# coils.net
KiCad netlist of a schematic drawn in Altium Designer
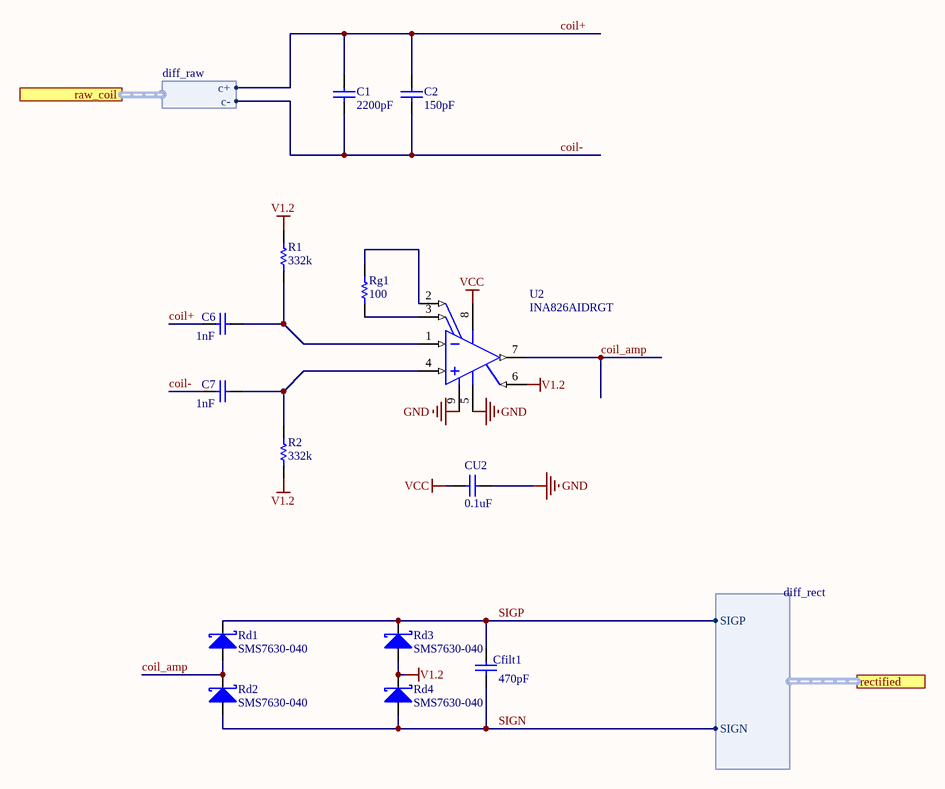
[diagram p0: coils.SchDoc]

(export (version "E")
  (design (tool "Eeschema 10.0.6"))
  (components
    (comp (ref "C1")
      (value "2200pF")
      (footprint "0402")
      (description "Ceramic Capacitor (Surface Mount)")
      (fields (field (name "MANUFACTURER") "Generic Ceramic Chip Cap (TBD)") (field (name "Comment") "Cap"))
      (libsource (lib "maglib") (part "Cap"))
    )
    (comp (ref "C2")
      (value "150pF")
      (footprint "0402")
      (description "Ceramic Capacitor (Surface Mount)")
      (fields (field (name "MANUFACTURER") "Generic Ceramic Chip Cap (TBD)") (field (name "Comment") "Cap"))
      (libsource (lib "maglib") (part "Cap"))
    )
    (comp (ref "C6")
      (value "1nF")
      (footprint "0402")
      (description "Ceramic Capacitor (Surface Mount)")
      (fields (field (name "MANUFACTURER") "Generic Ceramic Chip Cap (TBD)") (field (name "Comment") "Cap"))
      (libsource (lib "maglib") (part "Cap"))
    )
    (comp (ref "C7")
      (value "1nF")
      (footprint "0402")
      (description "Ceramic Capacitor (Surface Mount)")
      (fields (field (name "MANUFACTURER") "Generic Ceramic Chip Cap (TBD)") (field (name "Comment") "Cap"))
      (libsource (lib "maglib") (part "Cap"))
    )
    (comp (ref "Cfilt1")
      (value "470pF")
      (footprint "0402")
      (description "Ceramic Capacitor (Surface Mount)")
      (fields (field (name "MANUFACTURER") "Generic Ceramic Chip Cap (TBD)") (field (name "Comment") "Cap"))
      (libsource (lib "maglib") (part "Cap"))
    )
    (comp (ref "CU2")
      (value "0.1uF")
      (footprint "0402")
      (description "Ceramic Capacitor (Surface Mount)")
      (fields (field (name "MANUFACTURER") "Generic Ceramic Chip Cap (TBD)") (field (name "Comment") "Cap"))
      (libsource (lib "maglib") (part "Cap"))
    )
    (comp (ref "R1")
      (value "332k")
      (footprint "0402")
      (description "Chip Resistor (Surface Mount)")
      (fields (field (name "MANUFACTURER") "Generic Chip Res (TBD)") (field (name "Comment") "Res"))
      (libsource (lib "maglib") (part "Res"))
    )
    (comp (ref "R2")
      (value "332k")
      (footprint "0402")
      (description "Chip Resistor (Surface Mount)")
      (fields (field (name "MANUFACTURER") "Generic Chip Res (TBD)") (field (name "Comment") "Res"))
      (libsource (lib "maglib") (part "Res"))
    )
    (comp (ref "Rd1")
      (value "SMS7630-040")
      (footprint "0402")
      (libsource (lib "altium-import") (part "root_1_SMS7630-040_"))
    )
    (comp (ref "Rd2")
      (value "SMS7630-040")
      (footprint "0402")
      (libsource (lib "altium-import") (part "root_1_SMS7630-040_"))
    )
    (comp (ref "Rd3")
      (value "SMS7630-040")
      (footprint "0402")
      (libsource (lib "altium-import") (part "root_1_SMS7630-040_"))
    )
    (comp (ref "Rd4")
      (value "SMS7630-040")
      (footprint "0402")
      (libsource (lib "altium-import") (part "root_1_SMS7630-040_"))
    )
    (comp (ref "Rg1")
      (value "100")
      (footprint "0402")
      (description "Chip Resistor (Surface Mount)")
      (fields (field (name "MANUFACTURER") "Generic Chip Res (TBD)") (field (name "Comment") "Res"))
      (libsource (lib "maglib") (part "Res"))
    )
    (comp (ref "U2")
      (value "INA826AIDRGT")
      (footprint "DRG0008A_V")
      (fields (field (name "MANUFACTURER") "Texas Instruments"))
      (libsource (lib "Altium Content Vault") (part "TI-INA826DRG8-2000X1200TP"))
    )
  )
  (nets
    (net (code "3") (name "/SIGN") (class "Default")
      (node (ref "Cfilt1") (pin "1") (pinfunction "1_1") (pintype "passive"))
      (node (ref "Rd2") (pin "1") (pinfunction "A_1") (pintype "passive"))
      (node (ref "Rd4") (pin "1") (pinfunction "A_1") (pintype "passive"))
    )
    (net (code "4") (name "/SIGP") (class "Default")
      (node (ref "Cfilt1") (pin "2") (pinfunction "2_2") (pintype "passive"))
      (node (ref "Rd1") (pin "2") (pinfunction "K_2") (pintype "passive"))
      (node (ref "Rd3") (pin "2") (pinfunction "K_2") (pintype "passive"))
    )
    (net (code "5") (name "/coil+") (class "Default")
      (node (ref "C1") (pin "2") (pinfunction "2_2") (pintype "passive"))
      (node (ref "C2") (pin "2") (pinfunction "2_2") (pintype "passive"))
      (node (ref "C6") (pin "1") (pinfunction "1_1") (pintype "passive"))
    )
    (net (code "6") (name "/coil-") (class "Default")
      (node (ref "C1") (pin "1") (pinfunction "1_1") (pintype "passive"))
      (node (ref "C2") (pin "1") (pinfunction "1_1") (pintype "passive"))
      (node (ref "C7") (pin "1") (pinfunction "1_1") (pintype "passive"))
    )
    (net (code "7") (name "/coil_amp") (class "Default")
      (node (ref "Rd1") (pin "1") (pinfunction "A_1") (pintype "passive"))
      (node (ref "Rd2") (pin "2") (pinfunction "K_2") (pintype "passive"))
      (node (ref "U2") (pin "7") (pinfunction "VOUT_7") (pintype "output"))
    )
    (net (code "10") (name "GND") (class "Default")
      (node (ref "CU2") (pin "1") (pinfunction "1_1") (pintype "passive"))
      (node (ref "U2") (pin "5") (pinfunction "VS-_5") (pintype "power_in"))
      (node (ref "U2") (pin "9") (pinfunction "EP_9") (pintype "passive"))
    )
    (net (code "11") (name "Net-(Rg1-Pad1)") (class "Default")
      (node (ref "Rg1") (pin "1") (pinfunction "1_1") (pintype "passive"))
      (node (ref "U2") (pin "2") (pinfunction "RG_2") (pintype "input"))
    )
    (net (code "12") (name "Net-(Rg1-Pad2)") (class "Default")
      (node (ref "Rg1") (pin "2") (pinfunction "2_2") (pintype "passive"))
      (node (ref "U2") (pin "3") (pinfunction "RG_3") (pintype "input"))
    )
    (net (code "13") (name "Net-(U2-IN+)") (class "Default")
      (node (ref "C7") (pin "2") (pinfunction "2_2") (pintype "passive"))
      (node (ref "R2") (pin "2") (pinfunction "2_2") (pintype "passive"))
      (node (ref "U2") (pin "4") (pinfunction "IN+_4") (pintype "input"))
    )
    (net (code "14") (name "Net-(U2-IN-)") (class "Default")
      (node (ref "C6") (pin "2") (pinfunction "2_2") (pintype "passive"))
      (node (ref "R1") (pin "1") (pinfunction "1_1") (pintype "passive"))
      (node (ref "U2") (pin "1") (pinfunction "IN-_1") (pintype "input"))
    )
    (net (code "15") (name "V1.2") (class "Default")
      (node (ref "R1") (pin "2") (pinfunction "2_2") (pintype "passive"))
      (node (ref "R2") (pin "1") (pinfunction "1_1") (pintype "passive"))
      (node (ref "Rd3") (pin "1") (pinfunction "A_1") (pintype "passive"))
      (node (ref "Rd4") (pin "2") (pinfunction "K_2") (pintype "passive"))
      (node (ref "U2") (pin "6") (pinfunction "REF_6") (pintype "input"))
    )
    (net (code "16") (name "VCC") (class "Default")
      (node (ref "CU2") (pin "2") (pinfunction "2_2") (pintype "passive"))
      (node (ref "U2") (pin "8") (pinfunction "VS+_8") (pintype "power_in"))
    )
  )
)
